# LIXIE_II_V2.net
KiCad netlist of a schematic drawn in EAGLE
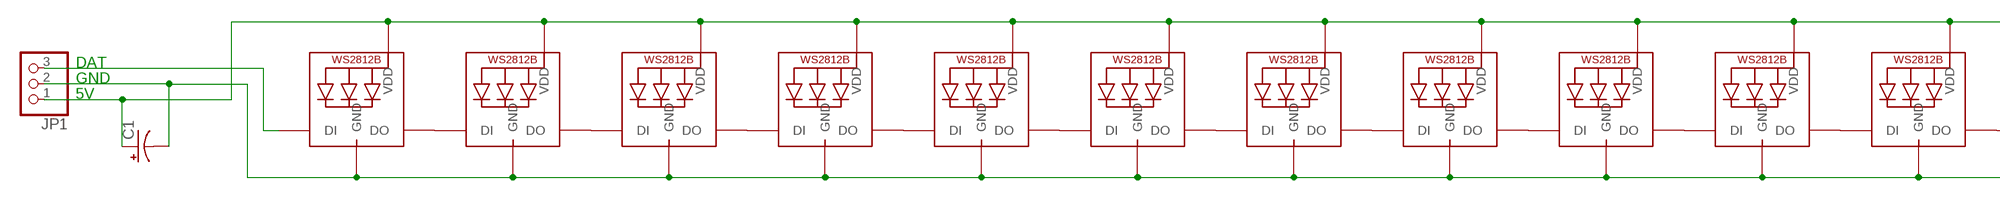
[diagram p0: schematic, sheet 1, part 1 of 2]
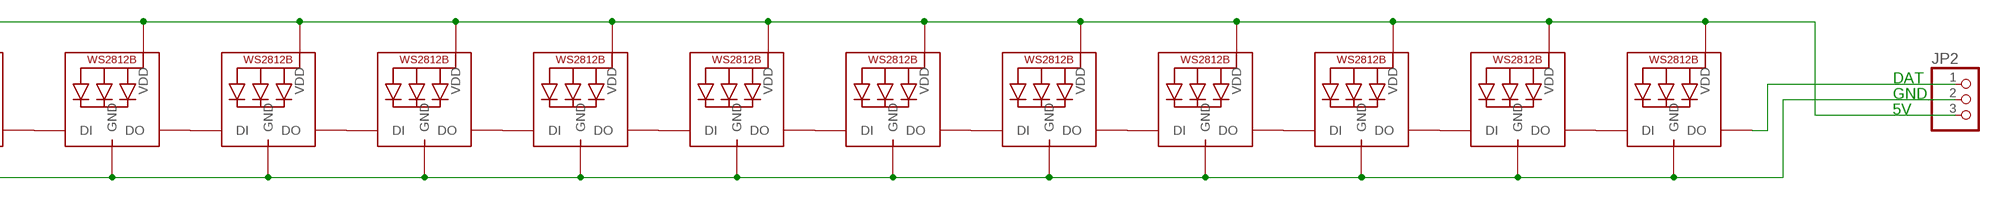
[diagram p1: schematic, sheet 1, part 2 of 2]

(export (version "E")
  (design (tool "Eeschema 10.0.6"))
  (components
    (comp (ref "C1")
      (value "CPOL-USE5-10.5")
      (footprint "eagle-import:E5-10,5")
      (libsource (lib "eagle-import") (part "CPOL-USE5-10.5"))
    )
    (comp (ref "JP1")
      (value "PINHD-1X3")
      (footprint "eagle-import:1X03")
      (libsource (lib "eagle-import") (part "PINHD-1X3"))
    )
    (comp (ref "JP2")
      (value "PINHD-1X3")
      (footprint "eagle-import:1X03")
      (libsource (lib "eagle-import") (part "PINHD-1X3"))
    )
    (comp (ref "LED1")
      (value "WS2812B_5050N")
      (footprint "eagle-import:WS2812B-NARROW")
      (libsource (lib "eagle-import") (part "WS2812B_5050N"))
    )
    (comp (ref "LED2")
      (value "WS2812B_5050N")
      (footprint "eagle-import:WS2812B-NARROW")
      (libsource (lib "eagle-import") (part "WS2812B_5050N"))
    )
    (comp (ref "LED3")
      (value "WS2812B_5050N")
      (footprint "eagle-import:WS2812B-NARROW")
      (libsource (lib "eagle-import") (part "WS2812B_5050N"))
    )
    (comp (ref "LED4")
      (value "WS2812B_5050N")
      (footprint "eagle-import:WS2812B-NARROW")
      (libsource (lib "eagle-import") (part "WS2812B_5050N"))
    )
    (comp (ref "LED5")
      (value "WS2812B_5050N")
      (footprint "eagle-import:WS2812B-NARROW")
      (libsource (lib "eagle-import") (part "WS2812B_5050N"))
    )
    (comp (ref "LED6")
      (value "WS2812B_5050N")
      (footprint "eagle-import:WS2812B-NARROW")
      (libsource (lib "eagle-import") (part "WS2812B_5050N"))
    )
    (comp (ref "LED7")
      (value "WS2812B_5050N")
      (footprint "eagle-import:WS2812B-NARROW")
      (libsource (lib "eagle-import") (part "WS2812B_5050N"))
    )
    (comp (ref "LED8")
      (value "WS2812B_5050N")
      (footprint "eagle-import:WS2812B-NARROW")
      (libsource (lib "eagle-import") (part "WS2812B_5050N"))
    )
    (comp (ref "LED9")
      (value "WS2812B_5050N")
      (footprint "eagle-import:WS2812B-NARROW")
      (libsource (lib "eagle-import") (part "WS2812B_5050N"))
    )
    (comp (ref "LED10")
      (value "WS2812B_5050N")
      (footprint "eagle-import:WS2812B-NARROW")
      (libsource (lib "eagle-import") (part "WS2812B_5050N"))
    )
    (comp (ref "LED11")
      (value "WS2812B_5050N")
      (footprint "eagle-import:WS2812B-NARROW")
      (libsource (lib "eagle-import") (part "WS2812B_5050N"))
    )
    (comp (ref "LED12")
      (value "WS2812B_5050N")
      (footprint "eagle-import:WS2812B-NARROW")
      (libsource (lib "eagle-import") (part "WS2812B_5050N"))
    )
    (comp (ref "LED13")
      (value "WS2812B_5050N")
      (footprint "eagle-import:WS2812B-NARROW")
      (libsource (lib "eagle-import") (part "WS2812B_5050N"))
    )
    (comp (ref "LED14")
      (value "WS2812B_5050N")
      (footprint "eagle-import:WS2812B-NARROW")
      (libsource (lib "eagle-import") (part "WS2812B_5050N"))
    )
    (comp (ref "LED15")
      (value "WS2812B_5050N")
      (footprint "eagle-import:WS2812B-NARROW")
      (libsource (lib "eagle-import") (part "WS2812B_5050N"))
    )
    (comp (ref "LED16")
      (value "WS2812B_5050N")
      (footprint "eagle-import:WS2812B-NARROW")
      (libsource (lib "eagle-import") (part "WS2812B_5050N"))
    )
    (comp (ref "LED17")
      (value "WS2812B_5050N")
      (footprint "eagle-import:WS2812B-NARROW")
      (libsource (lib "eagle-import") (part "WS2812B_5050N"))
    )
    (comp (ref "LED18")
      (value "WS2812B_5050N")
      (footprint "eagle-import:WS2812B-NARROW")
      (libsource (lib "eagle-import") (part "WS2812B_5050N"))
    )
    (comp (ref "LED19")
      (value "WS2812B_5050N")
      (footprint "eagle-import:WS2812B-NARROW")
      (libsource (lib "eagle-import") (part "WS2812B_5050N"))
    )
    (comp (ref "LED20")
      (value "WS2812B_5050N")
      (footprint "eagle-import:WS2812B-NARROW")
      (libsource (lib "eagle-import") (part "WS2812B_5050N"))
    )
    (comp (ref "LED21")
      (value "WS2812B_5050N")
      (footprint "eagle-import:WS2812B-NARROW")
      (libsource (lib "eagle-import") (part "WS2812B_5050N"))
    )
    (comp (ref "LED22")
      (value "WS2812B_5050N")
      (footprint "eagle-import:WS2812B-NARROW")
      (libsource (lib "eagle-import") (part "WS2812B_5050N"))
    )
  )
  (nets
    (net (code "1") (name "Net-(LED1-DI)") (class "Default")
      (node (ref "JP1") (pin "3") (pinfunction "3_3") (pintype "passive"))
      (node (ref "LED1") (pin "4-DIN") (pinfunction "DI_4-DIN") (pintype "input"))
    )
    (net (code "2") (name "Net-(LED1-DO)") (class "Default")
      (node (ref "LED1") (pin "2-DOUT") (pinfunction "DO_2-DOUT") (pintype "output"))
      (node (ref "LED2") (pin "4-DIN") (pinfunction "DI_4-DIN") (pintype "input"))
    )
    (net (code "3") (name "Net-(LED1-GND)") (class "Default")
      (node (ref "C1") (pin "-") (pinfunction "-_-") (pintype "passive"))
      (node (ref "JP1") (pin "2") (pinfunction "2_2") (pintype "passive"))
      (node (ref "JP2") (pin "2") (pinfunction "2_2") (pintype "passive"))
      (node (ref "LED1") (pin "3-GND") (pinfunction "GND_3-GND") (pintype "power_in"))
      (node (ref "LED10") (pin "3-GND") (pinfunction "GND_3-GND") (pintype "power_in"))
      (node (ref "LED11") (pin "3-GND") (pinfunction "GND_3-GND") (pintype "power_in"))
      (node (ref "LED12") (pin "3-GND") (pinfunction "GND_3-GND") (pintype "power_in"))
      (node (ref "LED13") (pin "3-GND") (pinfunction "GND_3-GND") (pintype "power_in"))
      (node (ref "LED14") (pin "3-GND") (pinfunction "GND_3-GND") (pintype "power_in"))
      (node (ref "LED15") (pin "3-GND") (pinfunction "GND_3-GND") (pintype "power_in"))
      (node (ref "LED16") (pin "3-GND") (pinfunction "GND_3-GND") (pintype "power_in"))
      (node (ref "LED17") (pin "3-GND") (pinfunction "GND_3-GND") (pintype "power_in"))
      (node (ref "LED18") (pin "3-GND") (pinfunction "GND_3-GND") (pintype "power_in"))
      (node (ref "LED19") (pin "3-GND") (pinfunction "GND_3-GND") (pintype "power_in"))
      (node (ref "LED2") (pin "3-GND") (pinfunction "GND_3-GND") (pintype "power_in"))
      (node (ref "LED20") (pin "3-GND") (pinfunction "GND_3-GND") (pintype "power_in"))
      (node (ref "LED21") (pin "3-GND") (pinfunction "GND_3-GND") (pintype "power_in"))
      (node (ref "LED22") (pin "3-GND") (pinfunction "GND_3-GND") (pintype "power_in"))
      (node (ref "LED3") (pin "3-GND") (pinfunction "GND_3-GND") (pintype "power_in"))
      (node (ref "LED4") (pin "3-GND") (pinfunction "GND_3-GND") (pintype "power_in"))
      (node (ref "LED5") (pin "3-GND") (pinfunction "GND_3-GND") (pintype "power_in"))
      (node (ref "LED6") (pin "3-GND") (pinfunction "GND_3-GND") (pintype "power_in"))
      (node (ref "LED7") (pin "3-GND") (pinfunction "GND_3-GND") (pintype "power_in"))
      (node (ref "LED8") (pin "3-GND") (pinfunction "GND_3-GND") (pintype "power_in"))
      (node (ref "LED9") (pin "3-GND") (pinfunction "GND_3-GND") (pintype "power_in"))
    )
    (net (code "4") (name "Net-(LED1-VDD)") (class "Default")
      (node (ref "C1") (pin "+") (pinfunction "+_+") (pintype "passive"))
      (node (ref "JP1") (pin "1") (pinfunction "1_1") (pintype "passive"))
      (node (ref "JP2") (pin "3") (pinfunction "3_3") (pintype "passive"))
      (node (ref "LED1") (pin "1-VDD") (pinfunction "VDD_1-VDD") (pintype "power_in"))
      (node (ref "LED10") (pin "1-VDD") (pinfunction "VDD_1-VDD") (pintype "power_in"))
      (node (ref "LED11") (pin "1-VDD") (pinfunction "VDD_1-VDD") (pintype "power_in"))
      (node (ref "LED12") (pin "1-VDD") (pinfunction "VDD_1-VDD") (pintype "power_in"))
      (node (ref "LED13") (pin "1-VDD") (pinfunction "VDD_1-VDD") (pintype "power_in"))
      (node (ref "LED14") (pin "1-VDD") (pinfunction "VDD_1-VDD") (pintype "power_in"))
      (node (ref "LED15") (pin "1-VDD") (pinfunction "VDD_1-VDD") (pintype "power_in"))
      (node (ref "LED16") (pin "1-VDD") (pinfunction "VDD_1-VDD") (pintype "power_in"))
      (node (ref "LED17") (pin "1-VDD") (pinfunction "VDD_1-VDD") (pintype "power_in"))
      (node (ref "LED18") (pin "1-VDD") (pinfunction "VDD_1-VDD") (pintype "power_in"))
      (node (ref "LED19") (pin "1-VDD") (pinfunction "VDD_1-VDD") (pintype "power_in"))
      (node (ref "LED2") (pin "1-VDD") (pinfunction "VDD_1-VDD") (pintype "power_in"))
      (node (ref "LED20") (pin "1-VDD") (pinfunction "VDD_1-VDD") (pintype "power_in"))
      (node (ref "LED21") (pin "1-VDD") (pinfunction "VDD_1-VDD") (pintype "power_in"))
      (node (ref "LED22") (pin "1-VDD") (pinfunction "VDD_1-VDD") (pintype "power_in"))
      (node (ref "LED3") (pin "1-VDD") (pinfunction "VDD_1-VDD") (pintype "power_in"))
      (node (ref "LED4") (pin "1-VDD") (pinfunction "VDD_1-VDD") (pintype "power_in"))
      (node (ref "LED5") (pin "1-VDD") (pinfunction "VDD_1-VDD") (pintype "power_in"))
      (node (ref "LED6") (pin "1-VDD") (pinfunction "VDD_1-VDD") (pintype "power_in"))
      (node (ref "LED7") (pin "1-VDD") (pinfunction "VDD_1-VDD") (pintype "power_in"))
      (node (ref "LED8") (pin "1-VDD") (pinfunction "VDD_1-VDD") (pintype "power_in"))
      (node (ref "LED9") (pin "1-VDD") (pinfunction "VDD_1-VDD") (pintype "power_in"))
    )
    (net (code "5") (name "Net-(LED2-DO)") (class "Default")
      (node (ref "LED2") (pin "2-DOUT") (pinfunction "DO_2-DOUT") (pintype "output"))
      (node (ref "LED3") (pin "4-DIN") (pinfunction "DI_4-DIN") (pintype "input"))
    )
    (net (code "6") (name "Net-(LED3-DO)") (class "Default")
      (node (ref "LED3") (pin "2-DOUT") (pinfunction "DO_2-DOUT") (pintype "output"))
      (node (ref "LED4") (pin "4-DIN") (pinfunction "DI_4-DIN") (pintype "input"))
    )
    (net (code "7") (name "Net-(LED4-DO)") (class "Default")
      (node (ref "LED4") (pin "2-DOUT") (pinfunction "DO_2-DOUT") (pintype "output"))
      (node (ref "LED5") (pin "4-DIN") (pinfunction "DI_4-DIN") (pintype "input"))
    )
    (net (code "8") (name "Net-(LED5-DO)") (class "Default")
      (node (ref "LED5") (pin "2-DOUT") (pinfunction "DO_2-DOUT") (pintype "output"))
      (node (ref "LED6") (pin "4-DIN") (pinfunction "DI_4-DIN") (pintype "input"))
    )
    (net (code "9") (name "Net-(LED6-DO)") (class "Default")
      (node (ref "LED6") (pin "2-DOUT") (pinfunction "DO_2-DOUT") (pintype "output"))
      (node (ref "LED7") (pin "4-DIN") (pinfunction "DI_4-DIN") (pintype "input"))
    )
    (net (code "10") (name "Net-(LED7-DO)") (class "Default")
      (node (ref "LED7") (pin "2-DOUT") (pinfunction "DO_2-DOUT") (pintype "output"))
      (node (ref "LED8") (pin "4-DIN") (pinfunction "DI_4-DIN") (pintype "input"))
    )
    (net (code "11") (name "Net-(LED8-DO)") (class "Default")
      (node (ref "LED8") (pin "2-DOUT") (pinfunction "DO_2-DOUT") (pintype "output"))
      (node (ref "LED9") (pin "4-DIN") (pinfunction "DI_4-DIN") (pintype "input"))
    )
    (net (code "12") (name "Net-(LED10-DI)") (class "Default")
      (node (ref "LED10") (pin "4-DIN") (pinfunction "DI_4-DIN") (pintype "input"))
      (node (ref "LED9") (pin "2-DOUT") (pinfunction "DO_2-DOUT") (pintype "output"))
    )
    (net (code "13") (name "Net-(LED10-DO)") (class "Default")
      (node (ref "LED10") (pin "2-DOUT") (pinfunction "DO_2-DOUT") (pintype "output"))
      (node (ref "LED11") (pin "4-DIN") (pinfunction "DI_4-DIN") (pintype "input"))
    )
    (net (code "14") (name "Net-(LED11-DO)") (class "Default")
      (node (ref "LED11") (pin "2-DOUT") (pinfunction "DO_2-DOUT") (pintype "output"))
      (node (ref "LED12") (pin "4-DIN") (pinfunction "DI_4-DIN") (pintype "input"))
    )
    (net (code "15") (name "Net-(LED12-DO)") (class "Default")
      (node (ref "LED12") (pin "2-DOUT") (pinfunction "DO_2-DOUT") (pintype "output"))
      (node (ref "LED13") (pin "4-DIN") (pinfunction "DI_4-DIN") (pintype "input"))
    )
    (net (code "16") (name "Net-(LED13-DO)") (class "Default")
      (node (ref "LED13") (pin "2-DOUT") (pinfunction "DO_2-DOUT") (pintype "output"))
      (node (ref "LED14") (pin "4-DIN") (pinfunction "DI_4-DIN") (pintype "input"))
    )
    (net (code "17") (name "Net-(LED14-DO)") (class "Default")
      (node (ref "LED14") (pin "2-DOUT") (pinfunction "DO_2-DOUT") (pintype "output"))
      (node (ref "LED15") (pin "4-DIN") (pinfunction "DI_4-DIN") (pintype "input"))
    )
    (net (code "18") (name "Net-(LED15-DO)") (class "Default")
      (node (ref "LED15") (pin "2-DOUT") (pinfunction "DO_2-DOUT") (pintype "output"))
      (node (ref "LED16") (pin "4-DIN") (pinfunction "DI_4-DIN") (pintype "input"))
    )
    (net (code "19") (name "Net-(LED16-DO)") (class "Default")
      (node (ref "LED16") (pin "2-DOUT") (pinfunction "DO_2-DOUT") (pintype "output"))
      (node (ref "LED17") (pin "4-DIN") (pinfunction "DI_4-DIN") (pintype "input"))
    )
    (net (code "20") (name "Net-(LED17-DO)") (class "Default")
      (node (ref "LED17") (pin "2-DOUT") (pinfunction "DO_2-DOUT") (pintype "output"))
      (node (ref "LED18") (pin "4-DIN") (pinfunction "DI_4-DIN") (pintype "input"))
    )
    (net (code "21") (name "Net-(LED18-DO)") (class "Default")
      (node (ref "LED18") (pin "2-DOUT") (pinfunction "DO_2-DOUT") (pintype "output"))
      (node (ref "LED19") (pin "4-DIN") (pinfunction "DI_4-DIN") (pintype "input"))
    )
    (net (code "22") (name "Net-(LED19-DO)") (class "Default")
      (node (ref "LED19") (pin "2-DOUT") (pinfunction "DO_2-DOUT") (pintype "output"))
      (node (ref "LED20") (pin "4-DIN") (pinfunction "DI_4-DIN") (pintype "input"))
    )
    (net (code "23") (name "Net-(LED20-DO)") (class "Default")
      (node (ref "LED20") (pin "2-DOUT") (pinfunction "DO_2-DOUT") (pintype "output"))
      (node (ref "LED21") (pin "4-DIN") (pinfunction "DI_4-DIN") (pintype "input"))
    )
    (net (code "24") (name "Net-(LED21-DO)") (class "Default")
      (node (ref "LED21") (pin "2-DOUT") (pinfunction "DO_2-DOUT") (pintype "output"))
      (node (ref "LED22") (pin "4-DIN") (pinfunction "DI_4-DIN") (pintype "input"))
    )
    (net (code "25") (name "Net-(LED22-DO)") (class "Default")
      (node (ref "JP2") (pin "1") (pinfunction "1_1") (pintype "passive"))
      (node (ref "LED22") (pin "2-DOUT") (pinfunction "DO_2-DOUT") (pintype "output"))
    )
  )
)
